# Y1.net
KiCad netlist of a schematic drawn in Altium Designer
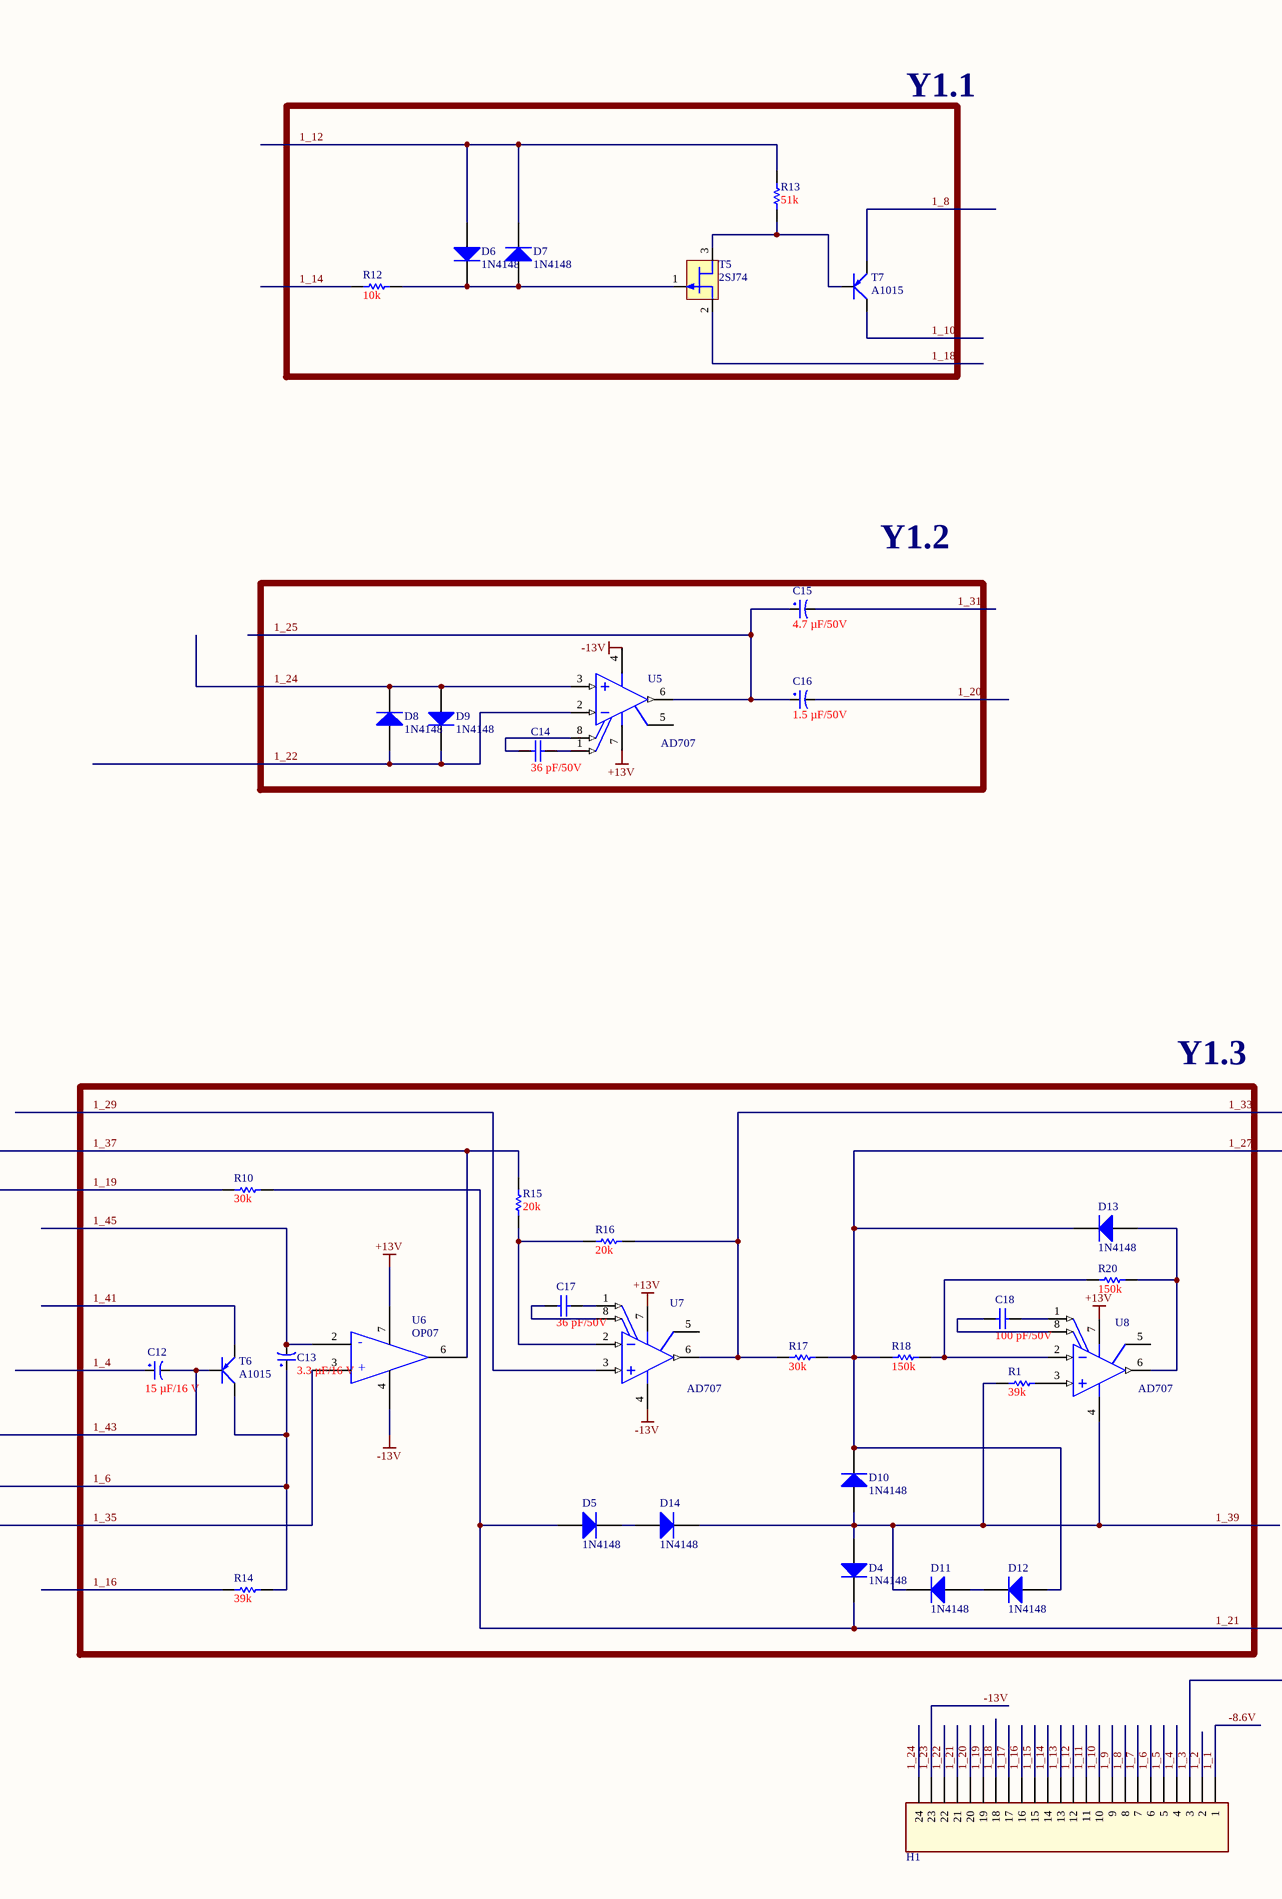
[diagram p0: Y1.SchDoc, left]
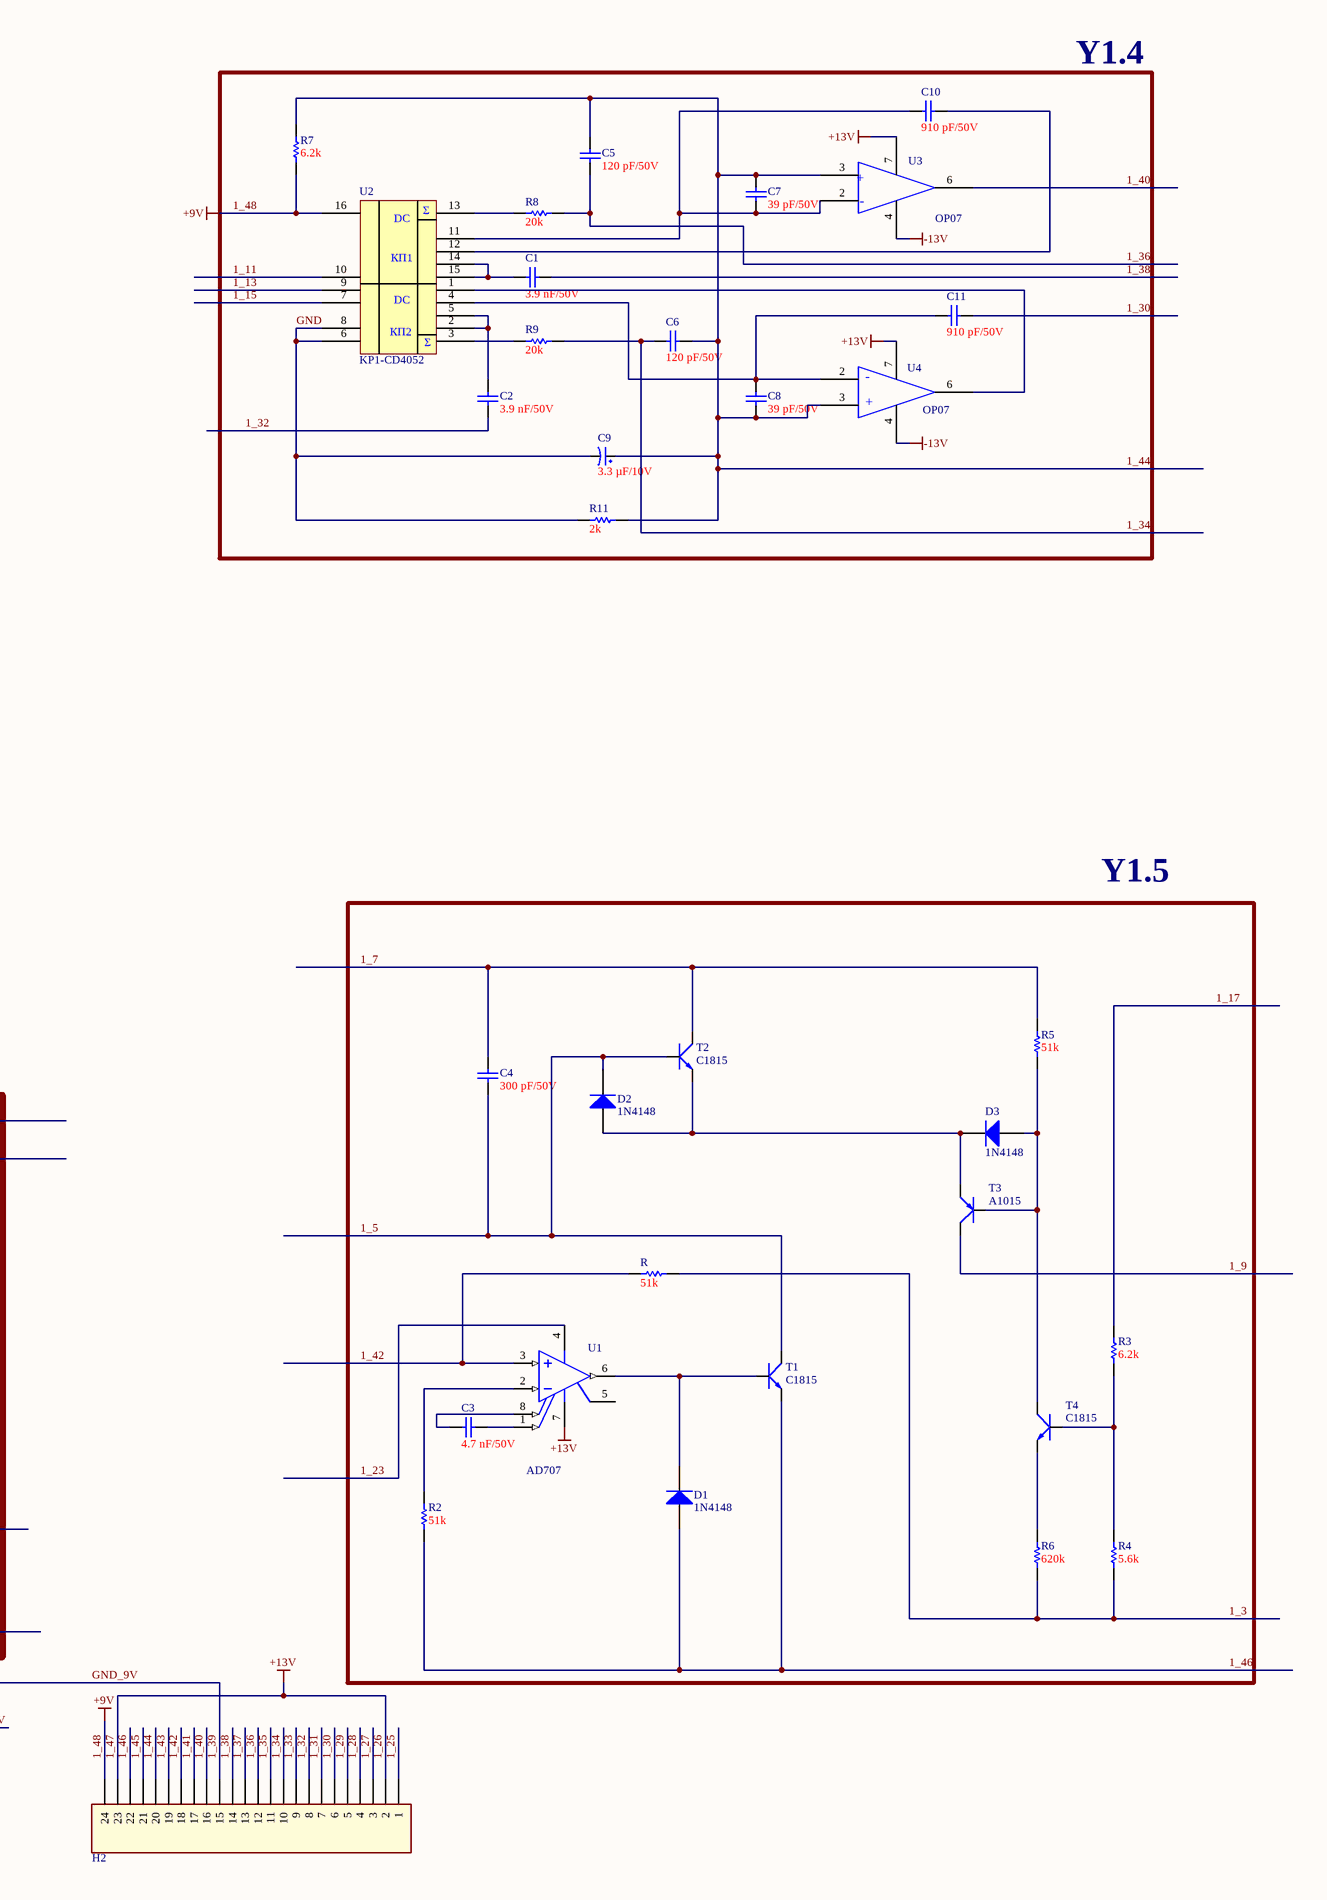
[diagram p1: Y1.SchDoc, right]

(export (version "E")
  (design (tool "Eeschema 10.0.6"))
  (components
    (comp (ref "C1")
      (value "3.9 nF/50V")
      (footprint "Masterit1805:C0805")
      (description "None polar capacitor")
      (fields (field (name "ASID PART NUMBER") "C-AS"))
      (libsource (lib "Mylib+Rev+4") (part "Cap ceramic"))
    )
    (comp (ref "C2")
      (value "3.9 nF/50V")
      (footprint "Masterit1805:C0805")
      (description "None polar capacitor")
      (fields (field (name "ASID PART NUMBER") "C-AS"))
      (libsource (lib "Mylib+Rev+4") (part "Cap ceramic"))
    )
    (comp (ref "C3")
      (value "4.7 nF/50V")
      (footprint "Masterit1805:C0805")
      (description "None polar capacitor")
      (fields (field (name "ASID PART NUMBER") "C-AS"))
      (libsource (lib "Mylib+Rev+4") (part "Cap ceramic"))
    )
    (comp (ref "C4")
      (value "300 pF/50V")
      (footprint "Masterit1805:C0805")
      (description "None polar capacitor")
      (fields (field (name "ASID PART NUMBER") "C-AS"))
      (libsource (lib "Mylib+Rev+4") (part "Cap ceramic"))
    )
    (comp (ref "C5")
      (value "120 pF/50V")
      (footprint "Masterit1805:C0805")
      (description "None polar capacitor")
      (fields (field (name "ASID PART NUMBER") "C-AS"))
      (libsource (lib "Mylib+Rev+4") (part "Cap ceramic"))
    )
    (comp (ref "C6")
      (value "120 pF/50V")
      (footprint "Masterit1805:C0805")
      (description "None polar capacitor")
      (fields (field (name "ASID PART NUMBER") "C-AS"))
      (libsource (lib "Mylib+Rev+4") (part "Cap ceramic"))
    )
    (comp (ref "C7")
      (value "39 pF/50V")
      (footprint "Masterit1805:C0805")
      (description "None polar capacitor")
      (fields (field (name "ASID PART NUMBER") "C-AS"))
      (libsource (lib "Mylib+Rev+4") (part "Cap ceramic"))
    )
    (comp (ref "C8")
      (value "39 pF/50V")
      (footprint "Masterit1805:C0805")
      (description "None polar capacitor")
      (fields (field (name "ASID PART NUMBER") "C-AS"))
      (libsource (lib "Mylib+Rev+4") (part "Cap ceramic"))
    )
    (comp (ref "C9")
      (value "3.3 µF/10V")
      (footprint "3216")
      (description "C 47uF/50V , 220uF/16V")
      (libsource (lib "syhaunguyen") (part "CP2"))
    )
    (comp (ref "C10")
      (value "910 pF/50V")
      (footprint "Masterit1805:C0805")
      (description "None polar capacitor")
      (fields (field (name "ASID PART NUMBER") "C-AS"))
      (libsource (lib "Mylib+Rev+4") (part "Cap ceramic"))
    )
    (comp (ref "C11")
      (value "910 pF/50V")
      (footprint "Masterit1805:C0805")
      (description "None polar capacitor")
      (fields (field (name "ASID PART NUMBER") "C-AS"))
      (libsource (lib "Mylib+Rev+4") (part "Cap ceramic"))
    )
    (comp (ref "C12")
      (value "15 µF/16 V")
      (footprint "LIB_EMBEDDED1805:smd 7343")
      (description "Cap P  0,1uF < 22uF , 16 - 50V")
      (libsource (lib "syhaunguyen") (part "CP1"))
    )
    (comp (ref "C13")
      (value "3.3 µF/16 V")
      (footprint "3216")
      (description "Cap P  0,1uF < 22uF , 16 - 50V")
      (libsource (lib "") (part "CP1_1"))
    )
    (comp (ref "C14")
      (value "36 pF/50V")
      (footprint "Masterit1805:C0805")
      (description "None polar capacitor")
      (fields (field (name "ASID PART NUMBER") "C-AS"))
      (libsource (lib "Mylib+Rev+4") (part "Cap ceramic"))
    )
    (comp (ref "C15")
      (value "4.7 µF/50V")
      (footprint "3216")
      (description "Cap P  0,1uF < 22uF , 16 - 50V")
      (libsource (lib "syhaunguyen") (part "CP1"))
    )
    (comp (ref "C16")
      (value "1.5 µF/50V")
      (footprint "3216")
      (description "Cap P  0,1uF < 22uF , 16 - 50V")
      (libsource (lib "syhaunguyen") (part "CP1"))
    )
    (comp (ref "C17")
      (value "36 pF/50V")
      (footprint "Masterit1805:C0805")
      (description "None polar capacitor")
      (fields (field (name "ASID PART NUMBER") "C-AS"))
      (libsource (lib "Mylib+Rev+4") (part "Cap ceramic"))
    )
    (comp (ref "C18")
      (value "100 pF/50V")
      (footprint "Masterit1805:C0805")
      (description "None polar capacitor")
      (fields (field (name "ASID PART NUMBER") "C-AS"))
      (libsource (lib "Mylib+Rev+4") (part "Cap ceramic"))
    )
    (comp (ref "D1")
      (value "1N4148")
      (footprint "SOD123")
      (description "Dán")
      (libsource (lib "Altium_Lib_by_KhueNguyenCreator") (part "Diode S4"))
    )
    (comp (ref "D2")
      (value "1N4148")
      (footprint "SOD123")
      (description "Dán")
      (libsource (lib "Altium_Lib_by_KhueNguyenCreator") (part "Diode S4"))
    )
    (comp (ref "D3")
      (value "1N4148")
      (footprint "SOD123")
      (description "Dán")
      (libsource (lib "Altium_Lib_by_KhueNguyenCreator") (part "Diode S4"))
    )
    (comp (ref "D4")
      (value "1N4148")
      (footprint "SOD123")
      (description "Dán")
      (libsource (lib "Altium_Lib_by_KhueNguyenCreator") (part "Diode S4"))
    )
    (comp (ref "D5")
      (value "1N4148")
      (footprint "SOD123")
      (description "Dán")
      (libsource (lib "Altium_Lib_by_KhueNguyenCreator") (part "Diode S4"))
    )
    (comp (ref "D6")
      (value "1N4148")
      (footprint "SOD123")
      (description "Dán")
      (libsource (lib "Altium_Lib_by_KhueNguyenCreator") (part "Diode S4"))
    )
    (comp (ref "D7")
      (value "1N4148")
      (footprint "SOD123")
      (description "Dán")
      (libsource (lib "Altium_Lib_by_KhueNguyenCreator") (part "Diode S4"))
    )
    (comp (ref "D8")
      (value "1N4148")
      (footprint "SOD123")
      (description "Dán")
      (libsource (lib "Altium_Lib_by_KhueNguyenCreator") (part "Diode S4"))
    )
    (comp (ref "D9")
      (value "1N4148")
      (footprint "SOD123")
      (description "Dán")
      (libsource (lib "Altium_Lib_by_KhueNguyenCreator") (part "Diode S4"))
    )
    (comp (ref "D10")
      (value "1N4148")
      (footprint "SOD123")
      (description "Dán")
      (libsource (lib "Altium_Lib_by_KhueNguyenCreator") (part "Diode S4"))
    )
    (comp (ref "D11")
      (value "1N4148")
      (footprint "SOD123")
      (description "Dán")
      (libsource (lib "Altium_Lib_by_KhueNguyenCreator") (part "Diode S4"))
    )
    (comp (ref "D12")
      (value "1N4148")
      (footprint "SOD123")
      (description "Dán")
      (libsource (lib "Altium_Lib_by_KhueNguyenCreator") (part "Diode S4"))
    )
    (comp (ref "D13")
      (value "1N4148")
      (footprint "SOD123")
      (description "Dán")
      (libsource (lib "Altium_Lib_by_KhueNguyenCreator") (part "Diode S4"))
    )
    (comp (ref "D14")
      (value "1N4148")
      (footprint "SOD123")
      (description "Dán")
      (libsource (lib "Altium_Lib_by_KhueNguyenCreator") (part "Diode S4"))
    )
    (comp (ref "H1")
      (value "Header 24")
      (footprint "header 24")
      (libsource (lib "LIB_EMBEDDED1805") (part "Header 24"))
    )
    (comp (ref "H2")
      (value "Header 24")
      (footprint "header 24")
      (libsource (lib "LIB_EMBEDDED1805") (part "Header 24"))
    )
    (comp (ref "R")
      (value "51k")
      (footprint "R0805")
      (description "Standard resistor")
      (fields (field (name "ASID PART NUMBER") "Res-AS"))
      (libsource (lib "Mylib+Rev+4") (part "Res"))
    )
    (comp (ref "R1")
      (value "39k")
      (footprint "R0805")
      (description "Standard resistor")
      (fields (field (name "ASID PART NUMBER") "Res-AS"))
      (libsource (lib "Mylib+Rev+4") (part "Res"))
    )
    (comp (ref "R2")
      (value "51k")
      (footprint "R0805")
      (description "Standard resistor")
      (fields (field (name "ASID PART NUMBER") "Res-AS"))
      (libsource (lib "Mylib+Rev+4") (part "Res"))
    )
    (comp (ref "R3")
      (value "6.2k")
      (footprint "R0805")
      (description "Standard resistor")
      (fields (field (name "ASID PART NUMBER") "Res-AS"))
      (libsource (lib "Mylib+Rev+4") (part "Res"))
    )
    (comp (ref "R4")
      (value "5.6k")
      (footprint "R0805")
      (description "Standard resistor")
      (fields (field (name "ASID PART NUMBER") "Res-AS"))
      (libsource (lib "Mylib+Rev+4") (part "Res"))
    )
    (comp (ref "R5")
      (value "51k")
      (footprint "R0805")
      (description "Standard resistor")
      (fields (field (name "ASID PART NUMBER") "Res-AS"))
      (libsource (lib "Mylib+Rev+4") (part "Res"))
    )
    (comp (ref "R6")
      (value "620k")
      (footprint "R0805")
      (description "Standard resistor")
      (fields (field (name "ASID PART NUMBER") "Res-AS"))
      (libsource (lib "Mylib+Rev+4") (part "Res"))
    )
    (comp (ref "R7")
      (value "6.2k")
      (footprint "R0805")
      (description "Standard resistor")
      (fields (field (name "ASID PART NUMBER") "Res-AS"))
      (libsource (lib "Mylib+Rev+4") (part "Res"))
    )
    (comp (ref "R8")
      (value "20k")
      (footprint "R0805")
      (description "Standard resistor")
      (fields (field (name "ASID PART NUMBER") "Res-AS"))
      (libsource (lib "Mylib+Rev+4") (part "Res"))
    )
    (comp (ref "R9")
      (value "20k")
      (footprint "R0805")
      (description "Standard resistor")
      (fields (field (name "ASID PART NUMBER") "Res-AS"))
      (libsource (lib "Mylib+Rev+4") (part "Res"))
    )
    (comp (ref "R10")
      (value "30k")
      (footprint "R0805")
      (description "Standard resistor")
      (fields (field (name "ASID PART NUMBER") "Res-AS"))
      (libsource (lib "Mylib+Rev+4") (part "Res"))
    )
    (comp (ref "R11")
      (value "2k")
      (footprint "R0805")
      (description "Standard resistor")
      (fields (field (name "ASID PART NUMBER") "Res-AS"))
      (libsource (lib "Mylib+Rev+4") (part "Res"))
    )
    (comp (ref "R12")
      (value "10k")
      (footprint "Masterit1805:R0805")
      (description "Standard resistor")
      (fields (field (name "ASID PART NUMBER") "Res-AS"))
      (libsource (lib "Mylib+Rev+4") (part "Res"))
    )
    (comp (ref "R13")
      (value "51k")
      (footprint "R0805")
      (description "Standard resistor")
      (fields (field (name "ASID PART NUMBER") "Res-AS"))
      (libsource (lib "Mylib+Rev+4") (part "Res"))
    )
    (comp (ref "R14")
      (value "39k")
      (footprint "Masterit1805:R0805")
      (description "Standard resistor")
      (fields (field (name "ASID PART NUMBER") "Res-AS"))
      (libsource (lib "Mylib+Rev+4") (part "Res"))
    )
    (comp (ref "R15")
      (value "20k")
      (footprint "Masterit1805:R0805")
      (description "Standard resistor")
      (fields (field (name "ASID PART NUMBER") "Res-AS"))
      (libsource (lib "Mylib+Rev+4") (part "Res"))
    )
    (comp (ref "R16")
      (value "20k")
      (footprint "R0805")
      (description "Standard resistor")
      (fields (field (name "ASID PART NUMBER") "Res-AS"))
      (libsource (lib "Mylib+Rev+4") (part "Res"))
    )
    (comp (ref "R17")
      (value "30k")
      (footprint "R0805")
      (description "Standard resistor")
      (fields (field (name "ASID PART NUMBER") "Res-AS"))
      (libsource (lib "Mylib+Rev+4") (part "Res"))
    )
    (comp (ref "R18")
      (value "150k")
      (footprint "R0805")
      (description "Standard resistor")
      (fields (field (name "ASID PART NUMBER") "Res-AS"))
      (libsource (lib "Mylib+Rev+4") (part "Res"))
    )
    (comp (ref "R20")
      (value "150k")
      (footprint "R0805")
      (description "Standard resistor")
      (fields (field (name "ASID PART NUMBER") "Res-AS"))
      (libsource (lib "Mylib+Rev+4") (part "Res"))
    )
    (comp (ref "T1")
      (value "C1815")
      (footprint "SOT-23")
      (description "SOT-23")
      (libsource (lib "Altium_Lib_by_KhueNguyenCreator") (part "Trans C1815 HF SMD"))
    )
    (comp (ref "T2")
      (value "C1815")
      (footprint "SOT-23")
      (description "SOT-23")
      (libsource (lib "Altium_Lib_by_KhueNguyenCreator") (part "Trans C1815 HF SMD"))
    )
    (comp (ref "T3")
      (value "A1015")
      (footprint "SOT-23")
      (description "PNP 600mW, ECB")
      (libsource (lib "Altium_Lib_by_KhueNguyenCreator") (part "Trans A1015 BA SMD"))
    )
    (comp (ref "T4")
      (value "C1815")
      (footprint "SOT-23")
      (description "SOT-23")
      (libsource (lib "Altium_Lib_by_KhueNguyenCreator") (part "Trans C1815 HF SMD"))
    )
    (comp (ref "T5") (value "2SJ74") (footprint "TO-92") (libsource (lib "thu vien") (part "JFET P CHANNEL")))
    (comp (ref "T6")
      (value "A1015")
      (footprint "SOT-23")
      (description "P 600mW, ECB")
      (libsource (lib "syhaunguyen") (part "PNP_ECB"))
    )
    (comp (ref "T7")
      (value "A1015")
      (footprint "SOT-23")
      (description "P 600mW, ECB")
      (libsource (lib "syhaunguyen") (part "PNP_ECB"))
    )
    (comp (ref "U1")
      (value "AD707")
      (footprint "SOIC8")
      (fields (field (name "MANUFACTURER") "Texas Instruments") (field (name "PARTNUMBER") "OP07DD"))
      (libsource (lib "TI Amplifiers and Linear Operational Amplifier General Purpose") (part "OP07DD"))
    )
    (comp (ref "U2")
      (value "KP1-CD4052")
      (footprint "soic16n")
      (libsource (lib "LIB_OF_PHONG") (part "KP1-CD4052"))
    )
    (comp (ref "U3") (value "OP07") (footprint "soic8") (libsource (lib "") (part "744UD1A/U1-4_1")))
    (comp (ref "U4")
      (value "OP07")
      (footprint "soic8")
      (libsource (lib "LIB_OF_PHONG") (part "744UD1A/U1-4"))
    )
    (comp (ref "U5")
      (value "AD707")
      (footprint "SOIC8")
      (fields (field (name "MANUFACTURER") "Texas Instruments") (field (name "PARTNUMBER") "OP07DD"))
      (libsource (lib "TI Amplifiers and Linear Operational Amplifier General Purpose") (part "OP07DD"))
    )
    (comp (ref "U6")
      (value "OP07")
      (footprint "soic8")
      (libsource (lib "LIB_OF_PHONG") (part "744UD1A/U1-4"))
    )
    (comp (ref "U7")
      (value "AD707")
      (footprint "SOIC8")
      (fields (field (name "MANUFACTURER") "Texas Instruments") (field (name "PARTNUMBER") "OP07DD"))
      (libsource (lib "TI Amplifiers and Linear Operational Amplifier General Purpose") (part "OP07DD"))
    )
    (comp (ref "U8")
      (value "AD707")
      (footprint "SOIC8")
      (fields (field (name "MANUFACTURER") "Texas Instruments") (field (name "PARTNUMBER") "OP07DD"))
      (libsource (lib "TI Amplifiers and Linear Operational Amplifier General Purpose") (part "OP07DD"))
    )
  )
  (nets
    (net (code "1") (name "+9V") (class "Default")
      (node (ref "H2") (pin "24") (pinfunction "24_24") (pintype "passive"))
      (node (ref "R7") (pin "1") (pinfunction "1_1") (pintype "passive"))
      (node (ref "U2") (pin "16") (pinfunction "16_16") (pintype "passive"))
    )
    (net (code "2") (name "+13V") (class "Default")
      (node (ref "H2") (pin "2") (pinfunction "2_2") (pintype "passive"))
      (node (ref "H2") (pin "23") (pinfunction "23_23") (pintype "passive"))
      (node (ref "U1") (pin "7") (pinfunction "VCC+_7") (pintype "power_in"))
      (node (ref "U3") (pin "7") (pinfunction "7_7") (pintype "passive"))
      (node (ref "U4") (pin "7") (pinfunction "7_7") (pintype "passive"))
      (node (ref "U5") (pin "7") (pinfunction "VCC+_7") (pintype "power_in"))
      (node (ref "U6") (pin "7") (pinfunction "7_7") (pintype "passive"))
      (node (ref "U7") (pin "7") (pinfunction "VCC+_7") (pintype "power_in"))
      (node (ref "U8") (pin "7") (pinfunction "VCC+_7") (pintype "power_in"))
    )
    (net (code "3") (name "-13V") (class "Default")
      (node (ref "H1") (pin "23") (pinfunction "23_23") (pintype "passive"))
      (node (ref "U1") (pin "4") (pinfunction "VCC-_4") (pintype "power_in"))
      (node (ref "U3") (pin "4") (pinfunction "4_4") (pintype "passive"))
      (node (ref "U4") (pin "4") (pinfunction "4_4") (pintype "passive"))
      (node (ref "U5") (pin "4") (pinfunction "VCC-_4") (pintype "power_in"))
      (node (ref "U6") (pin "4") (pinfunction "4_4") (pintype "passive"))
      (node (ref "U7") (pin "4") (pinfunction "VCC-_4") (pintype "power_in"))
    )
    (net (code "4") (name "/-8.6V") (class "Default")
      (node (ref "H1") (pin "1") (pinfunction "1_1") (pintype "passive"))
    )
    (net (code "5") (name "/1_2") (class "Default")
      (node (ref "H1") (pin "2") (pinfunction "2_2") (pintype "passive"))
    )
    (net (code "6") (name "/1_3") (class "Default")
      (node (ref "D10") (pin "1") (pinfunction "A_1") (pintype "passive"))
      (node (ref "D11") (pin "2") (pinfunction "K_2") (pintype "passive"))
      (node (ref "D14") (pin "2") (pinfunction "K_2") (pintype "passive"))
      (node (ref "D4") (pin "1") (pinfunction "A_1") (pintype "passive"))
      (node (ref "H1") (pin "3") (pinfunction "3_3") (pintype "passive"))
      (node (ref "H2") (pin "15") (pinfunction "15_15") (pintype "passive"))
      (node (ref "R") (pin "1") (pinfunction "1_1") (pintype "passive"))
      (node (ref "R1") (pin "2") (pinfunction "2_2") (pintype "passive"))
      (node (ref "R4") (pin "1") (pinfunction "1_1") (pintype "passive"))
      (node (ref "R6") (pin "2") (pinfunction "2_2") (pintype "passive"))
      (node (ref "U8") (pin "4") (pinfunction "VCC-_4") (pintype "power_in"))
    )
    (net (code "7") (name "/1_4") (class "Default")
      (node (ref "C12") (pin "1") (pinfunction "1_1") (pintype "passive"))
      (node (ref "H1") (pin "4") (pinfunction "4_4") (pintype "passive"))
    )
    (net (code "8") (name "/1_5") (class "Default")
      (node (ref "C4") (pin "2") (pinfunction "2_2") (pintype "passive"))
      (node (ref "D2") (pin "2") (pinfunction "K_2") (pintype "passive"))
      (node (ref "H1") (pin "5") (pinfunction "5_5") (pintype "passive"))
      (node (ref "T1") (pin "3") (pinfunction "C_3") (pintype "passive"))
      (node (ref "T2") (pin "1") (pinfunction "B_1") (pintype "passive"))
    )
    (net (code "9") (name "/1_6") (class "Default")
      (node (ref "C13") (pin "1") (pinfunction "1_1") (pintype "passive"))
      (node (ref "H1") (pin "6") (pinfunction "6_6") (pintype "passive"))
      (node (ref "R14") (pin "1") (pinfunction "1_1") (pintype "passive"))
      (node (ref "T6") (pin "2") (pinfunction "C_2") (pintype "passive"))
    )
    (net (code "10") (name "/1_7") (class "Default")
      (node (ref "C4") (pin "1") (pinfunction "1_1") (pintype "passive"))
      (node (ref "H1") (pin "7") (pinfunction "7_7") (pintype "passive"))
      (node (ref "R5") (pin "2") (pinfunction "2_2") (pintype "passive"))
      (node (ref "T2") (pin "3") (pinfunction "C_3") (pintype "passive"))
    )
    (net (code "11") (name "/1_8") (class "Default")
      (node (ref "H1") (pin "8") (pinfunction "8_8") (pintype "passive"))
      (node (ref "T7") (pin "1") (pinfunction "E_1") (pintype "passive"))
    )
    (net (code "12") (name "/1_9") (class "Default")
      (node (ref "H1") (pin "9") (pinfunction "9_9") (pintype "passive"))
      (node (ref "T3") (pin "3") (pinfunction "C_3") (pintype "passive"))
    )
    (net (code "13") (name "/1_10") (class "Default")
      (node (ref "H1") (pin "10") (pinfunction "10_10") (pintype "passive"))
      (node (ref "T7") (pin "2") (pinfunction "C_2") (pintype "passive"))
    )
    (net (code "14") (name "/1_11") (class "Default")
      (node (ref "H1") (pin "11") (pinfunction "11_11") (pintype "passive"))
      (node (ref "U2") (pin "10") (pinfunction "10_10") (pintype "passive"))
    )
    (net (code "15") (name "/1_12") (class "Default")
      (node (ref "D6") (pin "1") (pinfunction "A_1") (pintype "passive"))
      (node (ref "D7") (pin "2") (pinfunction "K_2") (pintype "passive"))
      (node (ref "H1") (pin "12") (pinfunction "12_12") (pintype "passive"))
      (node (ref "R13") (pin "1") (pinfunction "1_1") (pintype "passive"))
    )
    (net (code "16") (name "/1_13") (class "Default")
      (node (ref "H1") (pin "13") (pinfunction "13_13") (pintype "passive"))
      (node (ref "U2") (pin "9") (pinfunction "9_9") (pintype "passive"))
    )
    (net (code "17") (name "/1_14") (class "Default")
      (node (ref "H1") (pin "14") (pinfunction "14_14") (pintype "passive"))
      (node (ref "R12") (pin "1") (pinfunction "1_1") (pintype "passive"))
    )
    (net (code "18") (name "/1_15") (class "Default")
      (node (ref "H1") (pin "15") (pinfunction "15_15") (pintype "passive"))
      (node (ref "U2") (pin "7") (pinfunction "7_7") (pintype "passive"))
    )
    (net (code "19") (name "/1_16") (class "Default")
      (node (ref "H1") (pin "16") (pinfunction "16_16") (pintype "passive"))
      (node (ref "R14") (pin "2") (pinfunction "2_2") (pintype "passive"))
    )
    (net (code "20") (name "/1_17") (class "Default")
      (node (ref "H1") (pin "17") (pinfunction "17_17") (pintype "passive"))
      (node (ref "R3") (pin "2") (pinfunction "2_2") (pintype "passive"))
    )
    (net (code "21") (name "/1_18") (class "Default")
      (node (ref "H1") (pin "18") (pinfunction "18_18") (pintype "passive"))
      (node (ref "T5") (pin "2") (pinfunction "D_2") (pintype "passive"))
    )
    (net (code "22") (name "/1_19") (class "Default")
      (node (ref "H1") (pin "19") (pinfunction "19_19") (pintype "passive"))
      (node (ref "R10") (pin "2") (pinfunction "2_2") (pintype "passive"))
    )
    (net (code "23") (name "/1_20") (class "Default")
      (node (ref "C16") (pin "2") (pinfunction "2_2") (pintype "passive"))
      (node (ref "H1") (pin "20") (pinfunction "20_20") (pintype "passive"))
    )
    (net (code "24") (name "/1_21") (class "Default")
      (node (ref "D4") (pin "2") (pinfunction "K_2") (pintype "passive"))
      (node (ref "D5") (pin "1") (pinfunction "A_1") (pintype "passive"))
      (node (ref "H1") (pin "21") (pinfunction "21_21") (pintype "passive"))
      (node (ref "R10") (pin "1") (pinfunction "1_1") (pintype "passive"))
    )
    (net (code "25") (name "/1_22") (class "Default")
      (node (ref "D8") (pin "1") (pinfunction "A_1") (pintype "passive"))
      (node (ref "D9") (pin "2") (pinfunction "K_2") (pintype "passive"))
      (node (ref "H1") (pin "22") (pinfunction "22_22") (pintype "passive"))
      (node (ref "U5") (pin "2") (pinfunction "IN-_2") (pintype "input"))
    )
    (net (code "26") (name "/1_24") (class "Default")
      (node (ref "D8") (pin "2") (pinfunction "K_2") (pintype "passive"))
      (node (ref "D9") (pin "1") (pinfunction "A_1") (pintype "passive"))
      (node (ref "H1") (pin "24") (pinfunction "24_24") (pintype "passive"))
      (node (ref "U5") (pin "3") (pinfunction "IN+_3") (pintype "input"))
    )
    (net (code "27") (name "/1_25") (class "Default")
      (node (ref "C15") (pin "1") (pinfunction "1_1") (pintype "passive"))
      (node (ref "C16") (pin "1") (pinfunction "1_1") (pintype "passive"))
      (node (ref "H2") (pin "1") (pinfunction "1_1") (pintype "passive"))
      (node (ref "U5") (pin "6") (pinfunction "OUT_6") (pintype "output"))
    )
    (net (code "28") (name "/1_27") (class "Default")
      (node (ref "D10") (pin "2") (pinfunction "K_2") (pintype "passive"))
      (node (ref "D12") (pin "1") (pinfunction "A_1") (pintype "passive"))
      (node (ref "D13") (pin "2") (pinfunction "K_2") (pintype "passive"))
      (node (ref "H2") (pin "3") (pinfunction "3_3") (pintype "passive"))
      (node (ref "R17") (pin "1") (pinfunction "1_1") (pintype "passive"))
      (node (ref "R18") (pin "2") (pinfunction "2_2") (pintype "passive"))
    )
    (net (code "29") (name "/1_28") (class "Default")
      (node (ref "H2") (pin "4") (pinfunction "4_4") (pintype "passive"))
    )
    (net (code "30") (name "/1_29") (class "Default")
      (node (ref "H2") (pin "5") (pinfunction "5_5") (pintype "passive"))
      (node (ref "U7") (pin "3") (pinfunction "IN+_3") (pintype "input"))
    )
    (net (code "31") (name "/1_30") (class "Default")
      (node (ref "C11") (pin "2") (pinfunction "2_2") (pintype "passive"))
      (node (ref "H2") (pin "6") (pinfunction "6_6") (pintype "passive"))
    )
    (net (code "32") (name "/1_31") (class "Default")
      (node (ref "C15") (pin "2") (pinfunction "2_2") (pintype "passive"))
      (node (ref "H2") (pin "7") (pinfunction "7_7") (pintype "passive"))
    )
    (net (code "33") (name "/1_32") (class "Default")
      (node (ref "C2") (pin "2") (pinfunction "2_2") (pintype "passive"))
      (node (ref "H2") (pin "8") (pinfunction "8_8") (pintype "passive"))
    )
    (net (code "34") (name "/1_33") (class "Default")
      (node (ref "H2") (pin "9") (pinfunction "9_9") (pintype "passive"))
      (node (ref "R16") (pin "1") (pinfunction "1_1") (pintype "passive"))
      (node (ref "R17") (pin "2") (pinfunction "2_2") (pintype "passive"))
      (node (ref "U7") (pin "6") (pinfunction "OUT_6") (pintype "output"))
    )
    (net (code "35") (name "/1_34") (class "Default")
      (node (ref "C6") (pin "2") (pinfunction "2_2") (pintype "passive"))
      (node (ref "H2") (pin "10") (pinfunction "10_10") (pintype "passive"))
      (node (ref "R9") (pin "2") (pinfunction "2_2") (pintype "passive"))
    )
    (net (code "36") (name "/1_35") (class "Default")
      (node (ref "H2") (pin "11") (pinfunction "11_11") (pintype "passive"))
      (node (ref "U6") (pin "3") (pinfunction "3_3") (pintype "passive"))
    )
    (net (code "37") (name "/1_36") (class "Default")
      (node (ref "C5") (pin "2") (pinfunction "2_2") (pintype "passive"))
      (node (ref "H2") (pin "12") (pinfunction "12_12") (pintype "passive"))
      (node (ref "R8") (pin "2") (pinfunction "2_2") (pintype "passive"))
    )
    (net (code "38") (name "/1_37") (class "Default")
      (node (ref "H2") (pin "13") (pinfunction "13_13") (pintype "passive"))
      (node (ref "R15") (pin "1") (pinfunction "1_1") (pintype "passive"))
      (node (ref "U6") (pin "6") (pinfunction "6_6") (pintype "passive"))
    )
    (net (code "39") (name "/1_38") (class "Default")
      (node (ref "C1") (pin "1") (pinfunction "1_1") (pintype "passive"))
      (node (ref "H2") (pin "14") (pinfunction "14_14") (pintype "passive"))
    )
    (net (code "40") (name "/1_40") (class "Default")
      (node (ref "H2") (pin "16") (pinfunction "16_16") (pintype "passive"))
      (node (ref "U3") (pin "6") (pinfunction "6_6") (pintype "passive"))
    )
    (net (code "41") (name "/1_41") (class "Default")
      (node (ref "H2") (pin "17") (pinfunction "17_17") (pintype "passive"))
      (node (ref "T6") (pin "1") (pinfunction "E_1") (pintype "passive"))
    )
    (net (code "42") (name "/1_42") (class "Default")
      (node (ref "H2") (pin "18") (pinfunction "18_18") (pintype "passive"))
      (node (ref "R") (pin "2") (pinfunction "2_2") (pintype "passive"))
      (node (ref "U1") (pin "3") (pinfunction "IN+_3") (pintype "input"))
    )
    (net (code "43") (name "/1_43") (class "Default")
      (node (ref "C12") (pin "2") (pinfunction "2_2") (pintype "passive"))
      (node (ref "H2") (pin "19") (pinfunction "19_19") (pintype "passive"))
      (node (ref "T6") (pin "3") (pinfunction "B_3") (pintype "passive"))
    )
    (net (code "44") (name "/1_44") (class "Default")
      (node (ref "C5") (pin "1") (pinfunction "1_1") (pintype "passive"))
      (node (ref "C6") (pin "1") (pinfunction "1_1") (pintype "passive"))
      (node (ref "C7") (pin "1") (pinfunction "1_1") (pintype "passive"))
      (node (ref "C8") (pin "2") (pinfunction "2_2") (pintype "passive"))
      (node (ref "C9") (pin "1") (pinfunction "1_1") (pintype "passive"))
      (node (ref "H2") (pin "20") (pinfunction "20_20") (pintype "passive"))
      (node (ref "R11") (pin "1") (pinfunction "1_1") (pintype "passive"))
      (node (ref "R7") (pin "2") (pinfunction "2_2") (pintype "passive"))
      (node (ref "U3") (pin "3") (pinfunction "3_3") (pintype "passive"))
      (node (ref "U4") (pin "3") (pinfunction "3_3") (pintype "passive"))
    )
    (net (code "45") (name "/1_45") (class "Default")
      (node (ref "C13") (pin "2") (pinfunction "2_2") (pintype "passive"))
      (node (ref "H2") (pin "21") (pinfunction "21_21") (pintype "passive"))
      (node (ref "U6") (pin "2") (pinfunction "2_2") (pintype "passive"))
    )
    (net (code "46") (name "/1_46") (class "Default")
      (node (ref "D1") (pin "1") (pinfunction "A_1") (pintype "passive"))
      (node (ref "H2") (pin "22") (pinfunction "22_22") (pintype "passive"))
      (node (ref "R2") (pin "1") (pinfunction "1_1") (pintype "passive"))
      (node (ref "T1") (pin "2") (pinfunction "E_2") (pintype "passive"))
    )
    (net (code "47") (name "/GND") (class "Default")
      (node (ref "C9") (pin "2") (pinfunction "2_2") (pintype "passive"))
      (node (ref "R11") (pin "2") (pinfunction "2_2") (pintype "passive"))
      (node (ref "U2") (pin "6") (pinfunction "6_6") (pintype "passive"))
      (node (ref "U2") (pin "8") (pinfunction "8_8") (pintype "passive"))
    )
    (net (code "48") (name "Net-(C1-Pad2)") (class "Default")
      (node (ref "C1") (pin "2") (pinfunction "2_2") (pintype "passive"))
      (node (ref "U2") (pin "14") (pinfunction "14_14") (pintype "passive"))
      (node (ref "U2") (pin "15") (pinfunction "15_15") (pintype "passive"))
    )
    (net (code "49") (name "Net-(C2-Pad1)") (class "Default")
      (node (ref "C2") (pin "1") (pinfunction "1_1") (pintype "passive"))
      (node (ref "U2") (pin "2") (pinfunction "2_2") (pintype "passive"))
      (node (ref "U2") (pin "5") (pinfunction "5_5") (pintype "passive"))
    )
    (net (code "50") (name "Net-(C10-Pad1)") (class "Default")
      (node (ref "C10") (pin "1") (pinfunction "1_1") (pintype "passive"))
      (node (ref "C7") (pin "2") (pinfunction "2_2") (pintype "passive"))
      (node (ref "U2") (pin "11") (pinfunction "11_11") (pintype "passive"))
      (node (ref "U3") (pin "2") (pinfunction "2_2") (pintype "passive"))
    )
    (net (code "51") (name "Net-(C10-Pad2)") (class "Default")
      (node (ref "C10") (pin "2") (pinfunction "2_2") (pintype "passive"))
      (node (ref "U2") (pin "12") (pinfunction "12_12") (pintype "passive"))
    )
    (net (code "52") (name "Net-(C11-Pad1)") (class "Default")
      (node (ref "C11") (pin "1") (pinfunction "1_1") (pintype "passive"))
      (node (ref "C8") (pin "1") (pinfunction "1_1") (pintype "passive"))
      (node (ref "U2") (pin "4") (pinfunction "4_4") (pintype "passive"))
      (node (ref "U4") (pin "2") (pinfunction "2_2") (pintype "passive"))
    )
    (net (code "53") (name "Net-(D1-K)") (class "Default")
      (node (ref "D1") (pin "2") (pinfunction "K_2") (pintype "passive"))
      (node (ref "T1") (pin "1") (pinfunction "B_1") (pintype "passive"))
      (node (ref "U1") (pin "6") (pinfunction "OUT_6") (pintype "output"))
    )
    (net (code "54") (name "Net-(D2-A)") (class "Default")
      (node (ref "D2") (pin "1") (pinfunction "A_1") (pintype "passive"))
      (node (ref "D3") (pin "2") (pinfunction "K_2") (pintype "passive"))
      (node (ref "T2") (pin "2") (pinfunction "E_2") (pintype "passive"))
      (node (ref "T3") (pin "2") (pinfunction "E_2") (pintype "passive"))
    )
    (net (code "55") (name "Net-(D3-A)") (class "Default")
      (node (ref "D3") (pin "1") (pinfunction "A_1") (pintype "passive"))
      (node (ref "R5") (pin "1") (pinfunction "1_1") (pintype "passive"))
      (node (ref "T3") (pin "1") (pinfunction "B_1") (pintype "passive"))
      (node (ref "T4") (pin "3") (pinfunction "C_3") (pintype "passive"))
    )
    (net (code "56") (name "Net-(D6-K)") (class "Default")
      (node (ref "D6") (pin "2") (pinfunction "K_2") (pintype "passive"))
      (node (ref "D7") (pin "1") (pinfunction "A_1") (pintype "passive"))
      (node (ref "R12") (pin "2") (pinfunction "2_2") (pintype "passive"))
      (node (ref "T5") (pin "1") (pinfunction "G_1") (pintype "passive"))
    )
    (net (code "57") (name "Net-(D11-A)") (class "Default")
      (node (ref "D11") (pin "1") (pinfunction "A_1") (pintype "passive"))
      (node (ref "D12") (pin "2") (pinfunction "K_2") (pintype "passive"))
    )
    (net (code "58") (name "Net-(D13-A)") (class "Default")
      (node (ref "D13") (pin "1") (pinfunction "A_1") (pintype "passive"))
      (node (ref "R20") (pin "2") (pinfunction "2_2") (pintype "passive"))
      (node (ref "U8") (pin "6") (pinfunction "OUT_6") (pintype "output"))
    )
    (net (code "59") (name "Net-(D14-A)") (class "Default")
      (node (ref "D14") (pin "1") (pinfunction "A_1") (pintype "passive"))
      (node (ref "D5") (pin "2") (pinfunction "K_2") (pintype "passive"))
    )
    (net (code "60") (name "Net-(R8-Pad1)") (class "Default")
      (node (ref "R8") (pin "1") (pinfunction "1_1") (pintype "passive"))
      (node (ref "U2") (pin "13") (pinfunction "13_13") (pintype "passive"))
    )
    (net (code "61") (name "Net-(R9-Pad1)") (class "Default")
      (node (ref "R9") (pin "1") (pinfunction "1_1") (pintype "passive"))
      (node (ref "U2") (pin "3") (pinfunction "3_3") (pintype "passive"))
    )
    (net (code "62") (name "Net-(T4-B)") (class "Default")
      (node (ref "R3") (pin "1") (pinfunction "1_1") (pintype "passive"))
      (node (ref "R4") (pin "2") (pinfunction "2_2") (pintype "passive"))
      (node (ref "T4") (pin "1") (pinfunction "B_1") (pintype "passive"))
    )
    (net (code "63") (name "Net-(T4-E)") (class "Default")
      (node (ref "R6") (pin "1") (pinfunction "1_1") (pintype "passive"))
      (node (ref "T4") (pin "2") (pinfunction "E_2") (pintype "passive"))
    )
    (net (code "64") (name "Net-(T5-S)") (class "Default")
      (node (ref "R13") (pin "2") (pinfunction "2_2") (pintype "passive"))
      (node (ref "T5") (pin "3") (pinfunction "S_3") (pintype "passive"))
      (node (ref "T7") (pin "3") (pinfunction "B_3") (pintype "passive"))
    )
    (net (code "65") (name "Net-(U1-IN-)") (class "Default")
      (node (ref "R2") (pin "2") (pinfunction "2_2") (pintype "passive"))
      (node (ref "U1") (pin "2") (pinfunction "IN-_2") (pintype "input"))
    )
    (net (code "66") (name "Net-(U1-OFFSET_N1)") (class "Default")
      (node (ref "C3") (pin "1") (pinfunction "1_1") (pintype "passive"))
      (node (ref "U1") (pin "1") (pinfunction "OFFSET_N1_1") (pintype "input"))
    )
    (net (code "67") (name "Net-(U1-OFFSET_N2)") (class "Default")
      (node (ref "C3") (pin "2") (pinfunction "2_2") (pintype "passive"))
      (node (ref "U1") (pin "8") (pinfunction "OFFSET_N2_8") (pintype "input"))
    )
    (net (code "68") (name "Net-(U2-Pad1)") (class "Default")
      (node (ref "U2") (pin "1") (pinfunction "1_1") (pintype "passive"))
      (node (ref "U4") (pin "6") (pinfunction "6_6") (pintype "passive"))
    )
    (net (code "69") (name "Net-(U5-OFFSET_N1)") (class "Default")
      (node (ref "C14") (pin "1") (pinfunction "1_1") (pintype "passive"))
      (node (ref "U5") (pin "1") (pinfunction "OFFSET_N1_1") (pintype "input"))
    )
    (net (code "70") (name "Net-(U5-OFFSET_N2)") (class "Default")
      (node (ref "C14") (pin "2") (pinfunction "2_2") (pintype "passive"))
      (node (ref "U5") (pin "8") (pinfunction "OFFSET_N2_8") (pintype "input"))
    )
    (net (code "71") (name "Net-(U7-IN-)") (class "Default")
      (node (ref "R15") (pin "2") (pinfunction "2_2") (pintype "passive"))
      (node (ref "R16") (pin "2") (pinfunction "2_2") (pintype "passive"))
      (node (ref "U7") (pin "2") (pinfunction "IN-_2") (pintype "input"))
    )
    (net (code "72") (name "Net-(U7-OFFSET_N1)") (class "Default")
      (node (ref "C17") (pin "1") (pinfunction "1_1") (pintype "passive"))
      (node (ref "U7") (pin "1") (pinfunction "OFFSET_N1_1") (pintype "input"))
    )
    (net (code "73") (name "Net-(U7-OFFSET_N2)") (class "Default")
      (node (ref "C17") (pin "2") (pinfunction "2_2") (pintype "passive"))
      (node (ref "U7") (pin "8") (pinfunction "OFFSET_N2_8") (pintype "input"))
    )
    (net (code "74") (name "Net-(U8-IN+)") (class "Default")
      (node (ref "R1") (pin "1") (pinfunction "1_1") (pintype "passive"))
      (node (ref "U8") (pin "3") (pinfunction "IN+_3") (pintype "input"))
    )
    (net (code "75") (name "Net-(U8-IN-)") (class "Default")
      (node (ref "R18") (pin "1") (pinfunction "1_1") (pintype "passive"))
      (node (ref "R20") (pin "1") (pinfunction "1_1") (pintype "passive"))
      (node (ref "U8") (pin "2") (pinfunction "IN-_2") (pintype "input"))
    )
    (net (code "76") (name "Net-(U8-OFFSET_N1)") (class "Default")
      (node (ref "C18") (pin "1") (pinfunction "1_1") (pintype "passive"))
      (node (ref "U8") (pin "1") (pinfunction "OFFSET_N1_1") (pintype "input"))
    )
    (net (code "77") (name "Net-(U8-OFFSET_N2)") (class "Default")
      (node (ref "C18") (pin "2") (pinfunction "2_2") (pintype "passive"))
      (node (ref "U8") (pin "8") (pinfunction "OFFSET_N2_8") (pintype "input"))
    )
    (net (code "78") (name "unconnected-(U1-NC-Pad5)") (class "Default")
      (node (ref "U1") (pin "5") (pinfunction "NC_5") (pintype "passive"))
    )
    (net (code "79") (name "unconnected-(U5-NC-Pad5)") (class "Default")
      (node (ref "U5") (pin "5") (pinfunction "NC_5") (pintype "passive"))
    )
    (net (code "80") (name "unconnected-(U7-NC-Pad5)") (class "Default")
      (node (ref "U7") (pin "5") (pinfunction "NC_5") (pintype "passive"))
    )
    (net (code "81") (name "unconnected-(U8-NC-Pad5)") (class "Default")
      (node (ref "U8") (pin "5") (pinfunction "NC_5") (pintype "passive"))
    )
  )
)
